# driver.net
KiCad netlist of a schematic drawn in Altium Designer
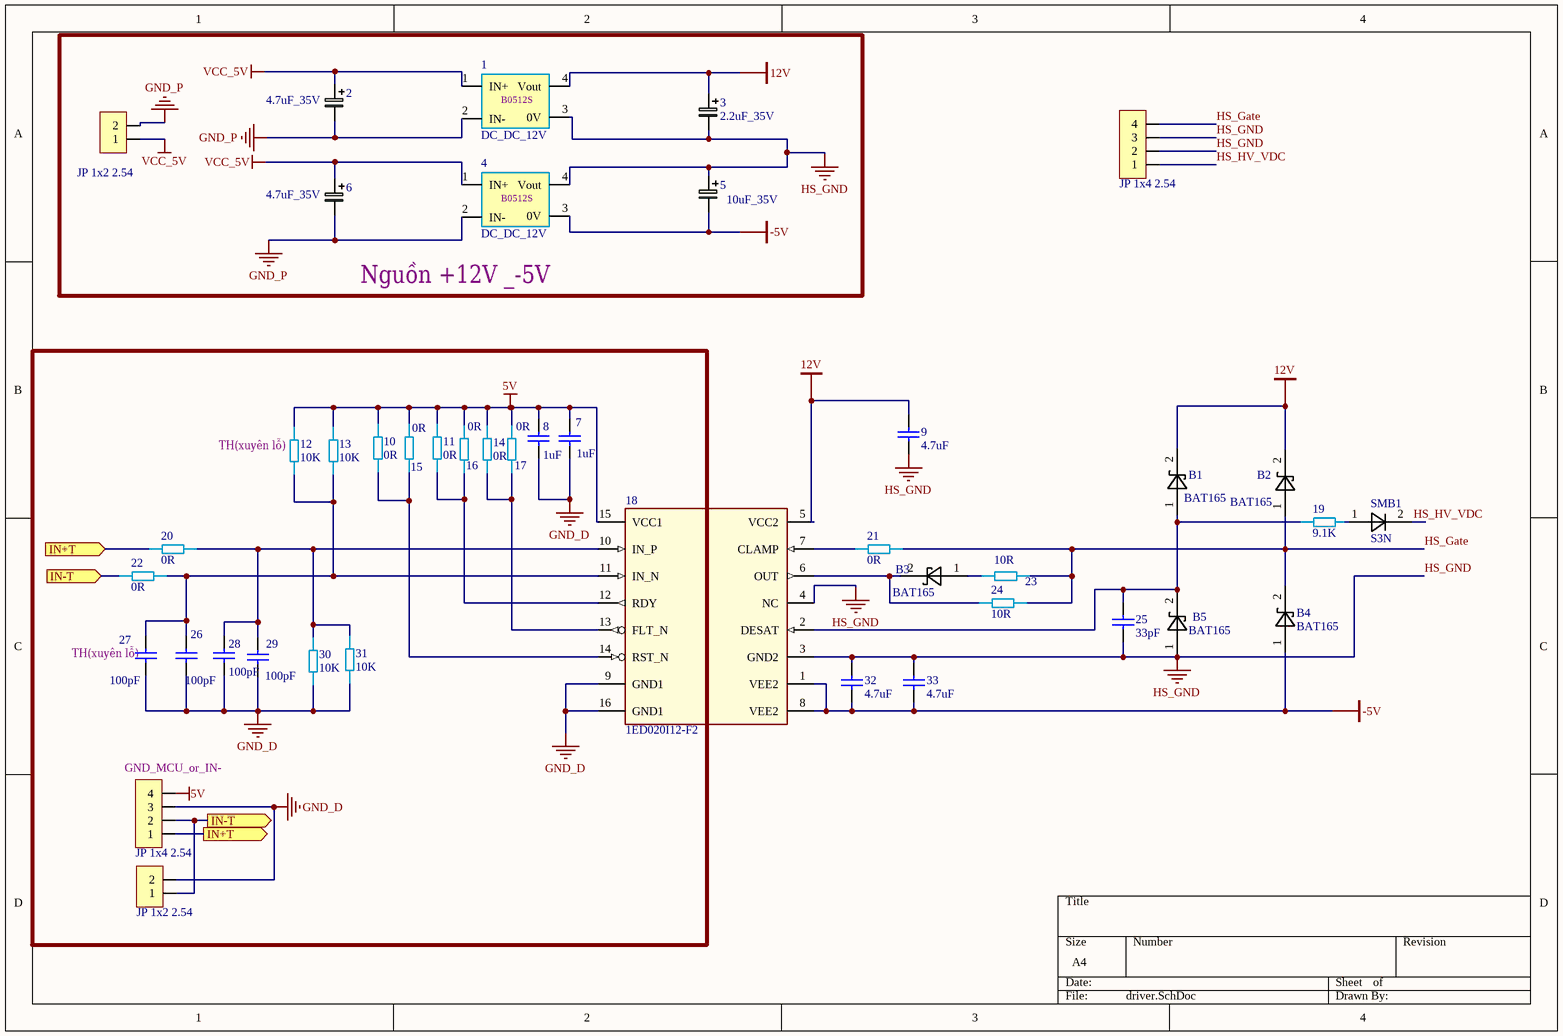
[diagram p0: driver.SchDoc]

(export (version "E")
  (design (tool "Eeschema 10.0.6"))
  (components
    (comp (ref "1")
      (value "DC_DC_12V")
      (footprint "B0512S/D-1W")
      (libsource (lib "labari_altium1") (part "DC_DC_12v"))
    )
    (comp (ref "2")
      (value "4.7uF_35V")
      (footprint "tu_4x5.4mm")
      (description "capacitor_electric")
      (libsource (lib "labari_altium1") (part "capacitor_electric"))
    )
    (comp (ref "3")
      (value "2.2uF_35V")
      (footprint "tu_4x5.4mm")
      (description "capacitor_electric")
      (libsource (lib "labari_altium1") (part "capacitor_electric"))
    )
    (comp (ref "4")
      (value "DC_DC_12V")
      (footprint "B0512S/D-1W")
      (libsource (lib "labari_altium1") (part "DC_DC_12v"))
    )
    (comp (ref "5")
      (value "10uF_35V")
      (footprint "tu_4x5.4mm")
      (description "capacitor_electric")
      (libsource (lib "labari_altium1") (part "capacitor_electric"))
    )
    (comp (ref "6")
      (value "4.7uF_35V")
      (footprint "tu_4x5.4mm")
      (description "capacitor_electric")
      (libsource (lib "labari_altium1") (part "capacitor_electric"))
    )
    (comp (ref "7")
      (value "1uF")
      (footprint "Tu 0805_N")
      (libsource (lib "labari_altium1") (part "cap_0805"))
    )
    (comp (ref "8")
      (value "1uF")
      (footprint "CAPR5.08-4x2.5")
      (description "Capacitor")
      (fields (field (name "PUBLISHER") "Altium Limited"))
      (libsource (lib "labari_altium1") (part "Cap_gom"))
    )
    (comp (ref "9")
      (value "4.7uF")
      (footprint "tu 1206_N")
      (libsource (lib "labari_altium1") (part "cap_1210"))
    )
    (comp (ref "10")
      (value "0R")
      (footprint "RES_Dung")
      (libsource (lib "labari_altium1") (part "311-0.0GRTR-ND"))
    )
    (comp (ref "11")
      (value "0R")
      (footprint "RES_Dung")
      (libsource (lib "labari_altium1") (part "311-0.0GRTR-ND"))
    )
    (comp (ref "12")
      (value "10K")
      (footprint "RES_Dung")
      (libsource (lib "labari_altium1") (part "311-0.0GRTR-ND"))
    )
    (comp (ref "13")
      (value "10K")
      (footprint "RES1206")
      (libsource (lib "labari_altium1") (part "311-0.0GRTR-ND"))
    )
    (comp (ref "14")
      (value "0R")
      (footprint "RES_Dung")
      (libsource (lib "labari_altium1") (part "311-0.0GRTR-ND"))
    )
    (comp (ref "15")
      (value "0R")
      (footprint "RES1206")
      (libsource (lib "labari_altium1") (part "311-0.0GRTR-ND"))
    )
    (comp (ref "16")
      (value "0R")
      (footprint "RES1206")
      (libsource (lib "labari_altium1") (part "311-0.0GRTR-ND"))
    )
    (comp (ref "17")
      (value "0R")
      (footprint "RES1206")
      (libsource (lib "labari_altium1") (part "311-0.0GRTR-ND"))
    )
    (comp (ref "18")
      (value "1ED020I12-F2")
      (footprint "SOIC127P1028X264-16N-1")
      (description "Single IGBT Driver IC")
      (fields (field (name "MANUFACTURER") "Infineon Technologies"))
      (libsource (lib "labari_altium1") (part "1ED020I12-F2"))
    )
    (comp (ref "19")
      (value "9.1K")
      (footprint "RES_2512")
      (libsource (lib "labari_altium1") (part "311-0.0GRTR-ND"))
    )
    (comp (ref "20")
      (value "0R")
      (footprint "RES1206")
      (libsource (lib "labari_altium1") (part "311-0.0GRTR-ND"))
    )
    (comp (ref "21")
      (value "0R")
      (footprint "RES_2512")
      (libsource (lib "labari_altium1") (part "311-0.0GRTR-ND"))
    )
    (comp (ref "22")
      (value "0R")
      (footprint "RES1206")
      (libsource (lib "labari_altium1") (part "311-0.0GRTR-ND"))
    )
    (comp (ref "23")
      (value "10R")
      (footprint "RES_2512")
      (libsource (lib "labari_altium1") (part "311-0.0GRTR-ND"))
    )
    (comp (ref "24")
      (value "10R")
      (footprint "RES_2512")
      (libsource (lib "labari_altium1") (part "311-0.0GRTR-ND"))
    )
    (comp (ref "25")
      (value "33pF")
      (footprint "Tu 0805_N")
      (libsource (lib "labari_altium1") (part "cap_0805"))
    )
    (comp (ref "26")
      (value "100pF")
      (footprint "Tu 0603")
      (libsource (lib "labari_altium1") (part "cap_0603"))
    )
    (comp (ref "27")
      (value "100pF")
      (footprint "CAPR5.08-4x2.5")
      (description "Capacitor")
      (fields (field (name "PUBLISHER") "Altium Limited"))
      (libsource (lib "labari_altium1") (part "Cap_gom"))
    )
    (comp (ref "28")
      (value "100pF")
      (footprint "CAPR5.08-4x2.5")
      (description "Capacitor")
      (fields (field (name "PUBLISHER") "Altium Limited"))
      (libsource (lib "labari_altium1") (part "Cap_gom"))
    )
    (comp (ref "29")
      (value "100pF")
      (footprint "Tu 0603")
      (libsource (lib "labari_altium1") (part "cap_0603"))
    )
    (comp (ref "30")
      (value "10K")
      (footprint "RES1206")
      (libsource (lib "labari_altium1") (part "311-0.0GRTR-ND"))
    )
    (comp (ref "31")
      (value "10K")
      (footprint "RES_Dung")
      (libsource (lib "labari_altium1") (part "311-0.0GRTR-ND"))
    )
    (comp (ref "32")
      (value "4.7uF")
      (footprint "tu 1206_N")
      (libsource (lib "labari_altium1") (part "cap_1210"))
    )
    (comp (ref "33")
      (value "4.7uF")
      (footprint "tu 1206_N")
      (libsource (lib "labari_altium1") (part "cap_1210"))
    )
    (comp (ref "34")
      (value "JP 1x2 2.54")
      (footprint "JP 1x2 DT_n")
      (description "Cắm")
      (libsource (lib "labari_altium1") (part "JP 1x2 2.54 Duc Thang"))
    )
    (comp (ref "B1")
      (value "BAT165")
      (footprint "BAT165E6327HTSA1TRND")
      (libsource (lib "labari_altium1") (part "BAT165"))
    )
    (comp (ref "B2")
      (value "BAT165")
      (footprint "BAT165E6327HTSA1TRND")
      (libsource (lib "labari_altium1") (part "BAT165"))
    )
    (comp (ref "B3")
      (value "BAT165")
      (footprint "BAT165E6327HTSA1TRND")
      (libsource (lib "labari_altium1") (part "BAT165"))
    )
    (comp (ref "B4")
      (value "BAT165")
      (footprint "BAT165E6327HTSA1TRND")
      (libsource (lib "labari_altium1") (part "BAT165"))
    )
    (comp (ref "B5")
      (value "BAT165")
      (footprint "BAT165E6327HTSA1TRND")
      (libsource (lib "labari_altium1") (part "BAT165"))
    )
    (comp (ref "HS_GATE1")
      (value "JP 1x4 2.54")
      (footprint "JP 1X4 DT_N")
      (description "Cắm")
      (libsource (lib "labari_altium1") (part "JP 1x4 2.54 Duc Thang"))
    )
    (comp (ref "IN+1")
      (value "JP 1x4 2.54")
      (footprint "JP 1X4 DT_N")
      (description "Cắm")
      (libsource (lib "labari_altium1") (part "JP 1x4 2.54 Duc Thang"))
    )
    (comp (ref "JP1")
      (value "JP 1x2 2.54")
      (footprint "JP 1x2 DT_n")
      (description "Cắm")
      (libsource (lib "labari_altium1") (part "JP 1x2 2.54 Duc Thang"))
    )
    (comp (ref "SMB1") (value "S3N") (footprint "SMB") (libsource (lib "labari_altium1") (part "S3A-S3N")))
  )
  (nets
    (net (code "1") (name "-5V") (class "Default")
      (node (ref "18") (pin "1") (pinfunction "VEE2_1") (pintype "power_in"))
      (node (ref "18") (pin "8") (pinfunction "VEE2_8") (pintype "power_in"))
      (node (ref "32") (pin "1") (pinfunction "1_1") (pintype "passive"))
      (node (ref "33") (pin "1") (pinfunction "1_1") (pintype "passive"))
      (node (ref "4") (pin "3") (pinfunction "0V_3") (pintype "passive"))
      (node (ref "5") (pin "2") (pinfunction "2_2") (pintype "passive"))
      (node (ref "B4") (pin "1") (pinfunction "1_1") (pintype "passive"))
    )
    (net (code "2") (name "/HS_Gate") (class "Default")
      (node (ref "21") (pin "2") (pinfunction "2_2") (pintype "passive"))
      (node (ref "23") (pin "2") (pinfunction "2_2") (pintype "passive"))
      (node (ref "24") (pin "2") (pinfunction "2_2") (pintype "passive"))
      (node (ref "B2") (pin "1") (pinfunction "1_1") (pintype "passive"))
      (node (ref "B4") (pin "2") (pinfunction "2_2") (pintype "passive"))
      (node (ref "HS_GATE1") (pin "4") (pinfunction "4_4") (pintype "passive"))
    )
    (net (code "3") (name "/HS_HV_VDC") (class "Default")
      (node (ref "HS_GATE1") (pin "1") (pinfunction "1_1") (pintype "passive"))
      (node (ref "SMB1") (pin "2") (pinfunction "2_2") (pintype "passive"))
    )
    (net (code "4") (name "/IN+T") (class "Default")
      (node (ref "20") (pin "1") (pinfunction "1_1") (pintype "passive"))
      (node (ref "IN+1") (pin "1") (pinfunction "1_1") (pintype "passive"))
    )
    (net (code "5") (name "/IN-T") (class "Default")
      (node (ref "22") (pin "1") (pinfunction "1_1") (pintype "passive"))
      (node (ref "34") (pin "1") (pinfunction "1_1") (pintype "passive"))
      (node (ref "IN+1") (pin "2") (pinfunction "2_2") (pintype "passive"))
    )
    (net (code "6") (name "5V") (class "Default")
      (node (ref "10") (pin "2") (pinfunction "2_2") (pintype "passive"))
      (node (ref "11") (pin "2") (pinfunction "2_2") (pintype "passive"))
      (node (ref "12") (pin "2") (pinfunction "2_2") (pintype "passive"))
      (node (ref "13") (pin "2") (pinfunction "2_2") (pintype "passive"))
      (node (ref "14") (pin "2") (pinfunction "2_2") (pintype "passive"))
      (node (ref "15") (pin "2") (pinfunction "2_2") (pintype "passive"))
      (node (ref "16") (pin "1") (pinfunction "1_1") (pintype "passive"))
      (node (ref "17") (pin "2") (pinfunction "2_2") (pintype "passive"))
      (node (ref "18") (pin "15") (pinfunction "VCC1_15") (pintype "power_in"))
      (node (ref "7") (pin "2") (pinfunction "2_2") (pintype "passive"))
      (node (ref "8") (pin "2") (pinfunction "2_2") (pintype "passive"))
      (node (ref "IN+1") (pin "4") (pinfunction "4_4") (pintype "passive"))
    )
    (net (code "7") (name "12V") (class "Default")
      (node (ref "1") (pin "4") (pinfunction "Vout_4") (pintype "passive"))
      (node (ref "18") (pin "5") (pinfunction "VCC2_5") (pintype "power_in"))
      (node (ref "3") (pin "1") (pinfunction "1_1") (pintype "passive"))
      (node (ref "9") (pin "2") (pinfunction "2_2") (pintype "passive"))
      (node (ref "B1") (pin "2") (pinfunction "2_2") (pintype "passive"))
      (node (ref "B2") (pin "2") (pinfunction "2_2") (pintype "passive"))
    )
    (net (code "8") (name "GND_D") (class "Default")
      (node (ref "18") (pin "16") (pinfunction "GND1_16") (pintype "power_in"))
      (node (ref "18") (pin "9") (pinfunction "GND1_9") (pintype "power_in"))
      (node (ref "26") (pin "1") (pinfunction "1_1") (pintype "passive"))
      (node (ref "27") (pin "1") (pinfunction "1_1") (pintype "passive"))
      (node (ref "28") (pin "1") (pinfunction "1_1") (pintype "passive"))
      (node (ref "29") (pin "1") (pinfunction "1_1") (pintype "passive"))
      (node (ref "30") (pin "1") (pinfunction "1_1") (pintype "passive"))
      (node (ref "31") (pin "1") (pinfunction "1_1") (pintype "passive"))
      (node (ref "34") (pin "2") (pinfunction "2_2") (pintype "passive"))
      (node (ref "7") (pin "1") (pinfunction "1_1") (pintype "passive"))
      (node (ref "8") (pin "1") (pinfunction "1_1") (pintype "passive"))
      (node (ref "IN+1") (pin "3") (pinfunction "3_3") (pintype "passive"))
    )
    (net (code "9") (name "GND_P") (class "Default")
      (node (ref "1") (pin "2") (pinfunction "IN-_2") (pintype "passive"))
      (node (ref "2") (pin "2") (pinfunction "2_2") (pintype "passive"))
      (node (ref "4") (pin "2") (pinfunction "IN-_2") (pintype "passive"))
      (node (ref "6") (pin "2") (pinfunction "2_2") (pintype "passive"))
      (node (ref "JP1") (pin "2") (pinfunction "2_2") (pintype "passive"))
    )
    (net (code "10") (name "HS_GND") (class "Default")
      (node (ref "1") (pin "3") (pinfunction "0V_3") (pintype "passive"))
      (node (ref "18") (pin "3") (pinfunction "GND2_3") (pintype "power_in"))
      (node (ref "18") (pin "4") (pinfunction "NC_4") (pintype "passive"))
      (node (ref "25") (pin "1") (pinfunction "1_1") (pintype "passive"))
      (node (ref "3") (pin "2") (pinfunction "2_2") (pintype "passive"))
      (node (ref "32") (pin "2") (pinfunction "2_2") (pintype "passive"))
      (node (ref "33") (pin "2") (pinfunction "2_2") (pintype "passive"))
      (node (ref "4") (pin "4") (pinfunction "Vout_4") (pintype "passive"))
      (node (ref "5") (pin "1") (pinfunction "1_1") (pintype "passive"))
      (node (ref "9") (pin "1") (pinfunction "1_1") (pintype "passive"))
      (node (ref "B5") (pin "1") (pinfunction "1_1") (pintype "passive"))
      (node (ref "HS_GATE1") (pin "2") (pinfunction "2_2") (pintype "passive"))
      (node (ref "HS_GATE1") (pin "3") (pinfunction "3_3") (pintype "passive"))
    )
    (net (code "11") (name "Net-(18-CLAMP)") (class "Default")
      (node (ref "18") (pin "7") (pinfunction "CLAMP_7") (pintype "input"))
      (node (ref "21") (pin "1") (pinfunction "1_1") (pintype "passive"))
    )
    (net (code "12") (name "Net-(18-DESAT)") (class "Default")
      (node (ref "18") (pin "2") (pinfunction "DESAT_2") (pintype "input"))
      (node (ref "19") (pin "1") (pinfunction "1_1") (pintype "passive"))
      (node (ref "25") (pin "2") (pinfunction "2_2") (pintype "passive"))
      (node (ref "B1") (pin "1") (pinfunction "1_1") (pintype "passive"))
      (node (ref "B5") (pin "2") (pinfunction "2_2") (pintype "passive"))
    )
    (net (code "13") (name "Net-(18-FLT_N)") (class "Default")
      (node (ref "14") (pin "1") (pinfunction "1_1") (pintype "passive"))
      (node (ref "17") (pin "1") (pinfunction "1_1") (pintype "passive"))
      (node (ref "18") (pin "13") (pinfunction "FLT_N_13") (pintype "output"))
    )
    (net (code "14") (name "Net-(18-IN_N)") (class "Default")
      (node (ref "12") (pin "1") (pinfunction "1_1") (pintype "passive"))
      (node (ref "13") (pin "1") (pinfunction "1_1") (pintype "passive"))
      (node (ref "18") (pin "11") (pinfunction "IN_N_11") (pintype "input"))
      (node (ref "22") (pin "2") (pinfunction "2_2") (pintype "passive"))
      (node (ref "26") (pin "2") (pinfunction "2_2") (pintype "passive"))
      (node (ref "27") (pin "2") (pinfunction "2_2") (pintype "passive"))
    )
    (net (code "15") (name "Net-(18-IN_P)") (class "Default")
      (node (ref "18") (pin "10") (pinfunction "IN_P_10") (pintype "input"))
      (node (ref "20") (pin "2") (pinfunction "2_2") (pintype "passive"))
      (node (ref "28") (pin "2") (pinfunction "2_2") (pintype "passive"))
      (node (ref "29") (pin "2") (pinfunction "2_2") (pintype "passive"))
      (node (ref "30") (pin "2") (pinfunction "2_2") (pintype "passive"))
      (node (ref "31") (pin "2") (pinfunction "2_2") (pintype "passive"))
    )
    (net (code "16") (name "Net-(18-OUT)") (class "Default")
      (node (ref "18") (pin "6") (pinfunction "OUT_6") (pintype "output"))
      (node (ref "24") (pin "1") (pinfunction "1_1") (pintype "passive"))
      (node (ref "B3") (pin "2") (pinfunction "2_2") (pintype "passive"))
    )
    (net (code "17") (name "Net-(18-RDY)") (class "Default")
      (node (ref "11") (pin "1") (pinfunction "1_1") (pintype "passive"))
      (node (ref "16") (pin "2") (pinfunction "2_2") (pintype "passive"))
      (node (ref "18") (pin "12") (pinfunction "RDY_12") (pintype "output"))
    )
    (net (code "18") (name "Net-(18-RST_N)") (class "Default")
      (node (ref "10") (pin "1") (pinfunction "1_1") (pintype "passive"))
      (node (ref "15") (pin "1") (pinfunction "1_1") (pintype "passive"))
      (node (ref "18") (pin "14") (pinfunction "RST_N_14") (pintype "input"))
    )
    (net (code "19") (name "Net-(19-Pad2)") (class "Default")
      (node (ref "19") (pin "2") (pinfunction "2_2") (pintype "passive"))
      (node (ref "SMB1") (pin "1") (pinfunction "1_1") (pintype "passive"))
    )
    (net (code "20") (name "Net-(23-Pad1)") (class "Default")
      (node (ref "23") (pin "1") (pinfunction "1_1") (pintype "passive"))
      (node (ref "B3") (pin "1") (pinfunction "1_1") (pintype "passive"))
    )
    (net (code "21") (name "VCC_5V") (class "Default")
      (node (ref "1") (pin "1") (pinfunction "IN+_1") (pintype "passive"))
      (node (ref "2") (pin "1") (pinfunction "1_1") (pintype "passive"))
      (node (ref "4") (pin "1") (pinfunction "IN+_1") (pintype "passive"))
      (node (ref "6") (pin "1") (pinfunction "1_1") (pintype "passive"))
      (node (ref "JP1") (pin "1") (pinfunction "1_1") (pintype "passive"))
    )
  )
)
